# L298.net
KiCad netlist of a schematic drawn in Altium Designer
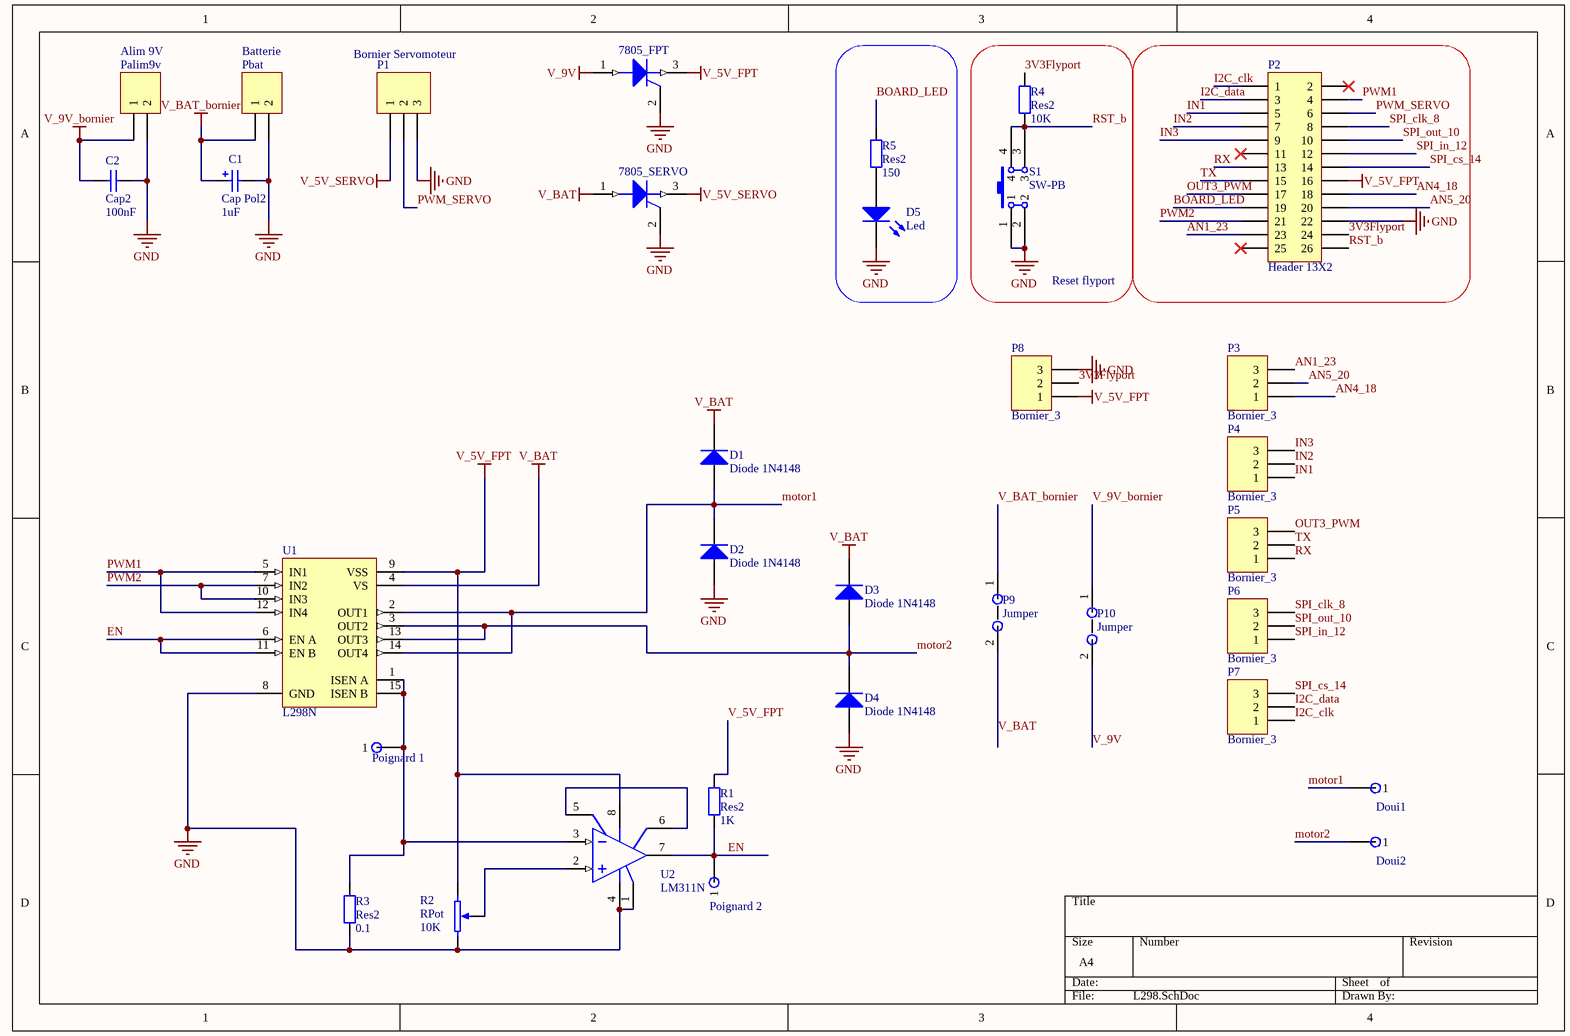
[diagram p0: L298.SchDoc]

(export (version "E")
  (design (tool "Eeschema 10.0.6"))
  (components
    (comp (ref "7805_FPT")
      (value "SCR")
      (footprint "TO-220-AB")
      (description "Silicon Controlled Rectifier")
      (fields (field (name "PUBLISHER") "Altium Limited"))
      (libsource (lib "Miscellaneous Devices") (part "SCR"))
    )
    (comp (ref "7805_SERVO")
      (value "SCR")
      (footprint "TO-220-AB")
      (description "Silicon Controlled Rectifier")
      (fields (field (name "PUBLISHER") "Altium Limited"))
      (libsource (lib "Miscellaneous Devices") (part "SCR"))
    )
    (comp (ref "C1")
      (value "Cap Pol2")
      (footprint "Capa2_pol")
      (description "Polarized Capacitor (Radial)")
      (fields (field (name "ALTIUM_VALUE") "1uF") (field (name "PUBLISHER") "Altium Limited"))
      (libsource (lib "LIBRAIRIE_INTEGREE_PHELMA1") (part "Cap Pol2"))
    )
    (comp (ref "C2")
      (value "Cap2")
      (footprint "CAPA2")
      (description "Capacitor")
      (fields (field (name "ALTIUM_VALUE") "100nF") (field (name "PUBLISHER") "Altium Limited"))
      (libsource (lib "LIBRAIRIE_INTEGREE_PHELMA1") (part "Cap2"))
    )
    (comp (ref "D1")
      (value "Diode 1N4148")
      (footprint "Ddiode")
      (description "High Conductance Fast Diode")
      (fields (field (name "PUBLISHER") "Altium Limited"))
      (libsource (lib "LIBRAIRIE_INTEGREE_PHELMA1") (part "Diode 1N4148"))
    )
    (comp (ref "D2")
      (value "Diode 1N4148")
      (footprint "Ddiode")
      (description "High Conductance Fast Diode")
      (fields (field (name "PUBLISHER") "Altium Limited"))
      (libsource (lib "LIBRAIRIE_INTEGREE_PHELMA1") (part "Diode 1N4148"))
    )
    (comp (ref "D3")
      (value "Diode 1N4148")
      (footprint "Ddiode")
      (description "High Conductance Fast Diode")
      (fields (field (name "PUBLISHER") "Altium Limited"))
      (libsource (lib "LIBRAIRIE_INTEGREE_PHELMA1") (part "Diode 1N4148"))
    )
    (comp (ref "D4")
      (value "Diode 1N4148")
      (footprint "Ddiode")
      (description "High Conductance Fast Diode")
      (fields (field (name "PUBLISHER") "Altium Limited"))
      (libsource (lib "LIBRAIRIE_INTEGREE_PHELMA1") (part "Diode 1N4148"))
    )
    (comp (ref "D5")
      (value "Led")
      (footprint "LED")
      (description "LED")
      (fields (field (name "PUBLISHER") "Altium Limited"))
      (libsource (lib "LIBRAIRIE_INTEGREE_PHELMA1") (part "Led"))
    )
    (comp (ref "Doui1")
      (value "douille_2mm")
      (footprint "Douille-2mm")
      (description "1-Pin")
      (fields (field (name "PUBLISHER") "Altium Limited"))
      (libsource (lib "INTEGRATED_LIBRARY1_CONNECTEURS") (part "douille_2mm"))
    )
    (comp (ref "Doui2")
      (value "douille_2mm")
      (footprint "Douille-2mm")
      (description "1-Pin")
      (fields (field (name "PUBLISHER") "Altium Limited"))
      (libsource (lib "INTEGRATED_LIBRARY1_CONNECTEURS") (part "douille_2mm"))
    )
    (comp (ref "P1")
      (value "Bornier Servomoteur")
      (footprint "Bornier_3")
      (description "Header, 3-Pin")
      (fields (field (name "PUBLISHER") "Altium Limited"))
      (libsource (lib "") (part "Bornier_3_1"))
    )
    (comp (ref "P2")
      (value "Header 13X2")
      (footprint "HDR2X13")
      (description "Header, 13-Pin, Dual row")
      (fields (field (name "PUBLISHER") "Altium Limited"))
      (libsource (lib "Miscellaneous Connectors") (part "Header 13X2"))
    )
    (comp (ref "P3")
      (value "Bornier_3")
      (footprint "Bornier_3")
      (description "Header, 3-Pin")
      (fields (field (name "PUBLISHER") "Altium Limited"))
      (libsource (lib "INTEGRATED_LIBRARY1_CONNECTEURS") (part "Bornier_3"))
    )
    (comp (ref "P4")
      (value "Bornier_3")
      (footprint "Bornier_3")
      (description "Header, 3-Pin")
      (fields (field (name "PUBLISHER") "Altium Limited"))
      (libsource (lib "INTEGRATED_LIBRARY1_CONNECTEURS") (part "Bornier_3"))
    )
    (comp (ref "P5")
      (value "Bornier_3")
      (footprint "Bornier_3")
      (description "Header, 3-Pin")
      (fields (field (name "PUBLISHER") "Altium Limited"))
      (libsource (lib "INTEGRATED_LIBRARY1_CONNECTEURS") (part "Bornier_3"))
    )
    (comp (ref "P6")
      (value "Bornier_3")
      (footprint "Bornier_3")
      (description "Header, 3-Pin")
      (fields (field (name "PUBLISHER") "Altium Limited"))
      (libsource (lib "INTEGRATED_LIBRARY1_CONNECTEURS") (part "Bornier_3"))
    )
    (comp (ref "P7")
      (value "Bornier_3")
      (footprint "Bornier_3")
      (description "Header, 3-Pin")
      (fields (field (name "PUBLISHER") "Altium Limited"))
      (libsource (lib "INTEGRATED_LIBRARY1_CONNECTEURS") (part "Bornier_3"))
    )
    (comp (ref "P8")
      (value "Bornier_3")
      (footprint "Bornier_3")
      (description "Header, 3-Pin")
      (fields (field (name "PUBLISHER") "Altium Limited"))
      (libsource (lib "INTEGRATED_LIBRARY1_CONNECTEURS") (part "Bornier_3"))
    )
    (comp (ref "P9")
      (value "Jumper")
      (footprint "picot2")
      (fields (field (name "PUBLISHER") "Altium Limited"))
      (libsource (lib "INTEGRATED_LIBRARY1_CONNECTEURS") (part "Jumper"))
    )
    (comp (ref "P10")
      (value "Jumper")
      (footprint "picot2")
      (fields (field (name "PUBLISHER") "Altium Limited"))
      (libsource (lib "INTEGRATED_LIBRARY1_CONNECTEURS") (part "Jumper"))
    )
    (comp (ref "Palim9v")
      (value "Alim 9V")
      (footprint "Bornier_2")
      (description "Header, 2-Pin")
      (fields (field (name "PUBLISHER") "Altium Limited"))
      (libsource (lib "INTEGRATED_LIBRARY1_CONNECTEURS") (part "Bornier_2"))
    )
    (comp (ref "Pbat")
      (value "Batterie")
      (footprint "Bornier_2")
      (description "Header, 2-Pin")
      (fields (field (name "PUBLISHER") "Altium Limited"))
      (libsource (lib "INTEGRATED_LIBRARY1_CONNECTEURS") (part "Bornier_2"))
    )
    (comp (ref "Poignard 1")
      (value "Poignard")
      (footprint "Poignard")
      (fields (field (name "PUBLISHER") "Altium Limited"))
      (libsource (lib "INTEGRATED_LIBRARY1_CONNECTEURS") (part "Poignard"))
    )
    (comp (ref "Poignard 2")
      (value "Poignard")
      (footprint "Poignard")
      (fields (field (name "PUBLISHER") "Altium Limited"))
      (libsource (lib "INTEGRATED_LIBRARY1_CONNECTEURS") (part "Poignard"))
    )
    (comp (ref "R1")
      (value "Res2")
      (footprint "res5_1/4W")
      (description "Resistor")
      (fields (field (name "ALTIUM_VALUE") "1K") (field (name "PUBLISHER") "Altium Limited"))
      (libsource (lib "") (part "Res2_1"))
    )
    (comp (ref "R2")
      (value "RPot")
      (footprint "AJUSTABLE")
      (description "Potentiometer")
      (fields (field (name "ALTIUM_VALUE") "10K") (field (name "PUBLISHER") "Altium Limited"))
      (libsource (lib "LIBRAIRIE_INTEGREE_PHELMA1") (part "RPot"))
    )
    (comp (ref "R3")
      (value "Res2")
      (footprint "res5_1/4W")
      (description "Resistor")
      (fields (field (name "ALTIUM_VALUE") "0.1") (field (name "PUBLISHER") "Altium Limited"))
      (libsource (lib "LIBRAIRIE_INTEGREE_PHELMA1") (part "Res2"))
    )
    (comp (ref "R4")
      (value "Res2")
      (footprint "res5_1/4W")
      (description "Resistor")
      (fields (field (name "ALTIUM_VALUE") "10K") (field (name "PUBLISHER") "Altium Limited"))
      (libsource (lib "LIBRAIRIE_INTEGREE_PHELMA1") (part "Res2"))
    )
    (comp (ref "R5")
      (value "Res2")
      (footprint "res5_1/4W")
      (description "Resistor")
      (fields (field (name "ALTIUM_VALUE") "150") (field (name "PUBLISHER") "Altium Limited"))
      (libsource (lib "LIBRAIRIE_INTEGREE_PHELMA1") (part "Res2"))
    )
    (comp (ref "S1")
      (value "SW-PB")
      (footprint "SW_BP")
      (description "Switch")
      (fields (field (name "PUBLISHER") "Altium Limited"))
      (libsource (lib "INTEGRATED_LIBRARY1_CONNECTEURS") (part "SW-PB"))
    )
    (comp (ref "U1")
      (value "L298N")
      (footprint "Multiwatt15V")
      (description "Dual Full Bridge Driver")
      (fields (field (name "PUBLISHER") "Altium Limited"))
      (libsource (lib "ST Interface DC Motor Controller") (part "L298N"))
    )
    (comp (ref "U2")
      (value "LM311N")
      (footprint "DIP8")
      (description "Voltage Comparator")
      (fields (field (name "PUBLISHER") "Altium Limited"))
      (libsource (lib "LIBRAIRIE_INTEGREE_PHELMA1") (part "LM311N"))
    )
  )
  (nets
    (net (code "1") (name "/3V3Flyport") (class "Default")
      (node (ref "P2") (pin "24") (pinfunction "24_24") (pintype "passive"))
      (node (ref "P8") (pin "2") (pinfunction "2_2") (pintype "passive"))
      (node (ref "R4") (pin "1") (pinfunction "1_1") (pintype "passive"))
    )
    (net (code "2") (name "/AN1_23") (class "Default")
      (node (ref "P2") (pin "23") (pinfunction "23_23") (pintype "passive"))
      (node (ref "P3") (pin "3") (pinfunction "3_3") (pintype "passive"))
    )
    (net (code "3") (name "/AN4_18") (class "Default")
      (node (ref "P2") (pin "18") (pinfunction "18_18") (pintype "passive"))
      (node (ref "P3") (pin "1") (pinfunction "1_1") (pintype "passive"))
    )
    (net (code "4") (name "/AN5_20") (class "Default")
      (node (ref "P2") (pin "20") (pinfunction "20_20") (pintype "passive"))
      (node (ref "P3") (pin "2") (pinfunction "2_2") (pintype "passive"))
    )
    (net (code "5") (name "/BOARD_LED") (class "Default")
      (node (ref "P2") (pin "19") (pinfunction "19_19") (pintype "passive"))
      (node (ref "R5") (pin "1") (pinfunction "1_1") (pintype "passive"))
    )
    (net (code "6") (name "/EN") (class "Default")
      (node (ref "Poignard 2") (pin "1") (pinfunction "1_1") (pintype "passive"))
      (node (ref "R1") (pin "1") (pinfunction "1_1") (pintype "passive"))
      (node (ref "U1") (pin "11") (pinfunction "EN_B_11") (pintype "input"))
      (node (ref "U1") (pin "6") (pinfunction "EN_A_6") (pintype "input"))
      (node (ref "U2") (pin "7") (pinfunction "OUT_7") (pintype "open_collector"))
    )
    (net (code "7") (name "/I2C_clk") (class "Default")
      (node (ref "P2") (pin "1") (pinfunction "1_1") (pintype "passive"))
      (node (ref "P7") (pin "1") (pinfunction "1_1") (pintype "passive"))
    )
    (net (code "8") (name "/I2C_data") (class "Default")
      (node (ref "P2") (pin "3") (pinfunction "3_3") (pintype "passive"))
      (node (ref "P7") (pin "2") (pinfunction "2_2") (pintype "passive"))
    )
    (net (code "9") (name "/IN1") (class "Default")
      (node (ref "P2") (pin "5") (pinfunction "5_5") (pintype "passive"))
      (node (ref "P4") (pin "1") (pinfunction "1_1") (pintype "passive"))
    )
    (net (code "10") (name "/IN2") (class "Default")
      (node (ref "P2") (pin "7") (pinfunction "7_7") (pintype "passive"))
      (node (ref "P4") (pin "2") (pinfunction "2_2") (pintype "passive"))
    )
    (net (code "11") (name "/IN3") (class "Default")
      (node (ref "P2") (pin "9") (pinfunction "9_9") (pintype "passive"))
      (node (ref "P4") (pin "3") (pinfunction "3_3") (pintype "passive"))
    )
    (net (code "12") (name "/OUT3_PWM") (class "Default")
      (node (ref "P2") (pin "17") (pinfunction "17_17") (pintype "passive"))
      (node (ref "P5") (pin "3") (pinfunction "3_3") (pintype "passive"))
    )
    (net (code "13") (name "/PWM1") (class "Default")
      (node (ref "P2") (pin "4") (pinfunction "4_4") (pintype "passive"))
      (node (ref "U1") (pin "12") (pinfunction "IN4_12") (pintype "input"))
      (node (ref "U1") (pin "5") (pinfunction "IN1_5") (pintype "input"))
    )
    (net (code "14") (name "/PWM2") (class "Default")
      (node (ref "P2") (pin "21") (pinfunction "21_21") (pintype "passive"))
      (node (ref "U1") (pin "10") (pinfunction "IN3_10") (pintype "input"))
      (node (ref "U1") (pin "7") (pinfunction "IN2_7") (pintype "input"))
    )
    (net (code "15") (name "/PWM_SERVO") (class "Default")
      (node (ref "P1") (pin "2") (pinfunction "2_2") (pintype "passive"))
      (node (ref "P2") (pin "6") (pinfunction "6_6") (pintype "passive"))
    )
    (net (code "16") (name "/RST_b") (class "Default")
      (node (ref "P2") (pin "26") (pinfunction "26_26") (pintype "passive"))
      (node (ref "R4") (pin "2") (pinfunction "2_2") (pintype "passive"))
      (node (ref "S1") (pin "3") (pinfunction "3_3") (pintype "passive"))
      (node (ref "S1") (pin "4") (pinfunction "4_4") (pintype "passive"))
    )
    (net (code "17") (name "/RX") (class "Default")
      (node (ref "P2") (pin "13") (pinfunction "13_13") (pintype "passive"))
      (node (ref "P5") (pin "1") (pinfunction "1_1") (pintype "passive"))
    )
    (net (code "18") (name "/SPI_clk_8") (class "Default")
      (node (ref "P2") (pin "8") (pinfunction "8_8") (pintype "passive"))
      (node (ref "P6") (pin "3") (pinfunction "3_3") (pintype "passive"))
    )
    (net (code "19") (name "/SPI_cs_14") (class "Default")
      (node (ref "P2") (pin "14") (pinfunction "14_14") (pintype "passive"))
      (node (ref "P7") (pin "3") (pinfunction "3_3") (pintype "passive"))
    )
    (net (code "20") (name "/SPI_in_12") (class "Default")
      (node (ref "P2") (pin "12") (pinfunction "12_12") (pintype "passive"))
      (node (ref "P6") (pin "1") (pinfunction "1_1") (pintype "passive"))
    )
    (net (code "21") (name "/SPI_out_10") (class "Default")
      (node (ref "P2") (pin "10") (pinfunction "10_10") (pintype "passive"))
      (node (ref "P6") (pin "2") (pinfunction "2_2") (pintype "passive"))
    )
    (net (code "22") (name "/TX") (class "Default")
      (node (ref "P2") (pin "15") (pinfunction "15_15") (pintype "passive"))
      (node (ref "P5") (pin "2") (pinfunction "2_2") (pintype "passive"))
    )
    (net (code "23") (name "/motor1") (class "Default")
      (node (ref "D1") (pin "1") (pinfunction "A_1") (pintype "passive"))
      (node (ref "D2") (pin "2") (pinfunction "K_2") (pintype "passive"))
      (node (ref "Doui1") (pin "1") (pinfunction "1_1") (pintype "passive"))
      (node (ref "U1") (pin "14") (pinfunction "OUT4_14") (pintype "output"))
      (node (ref "U1") (pin "2") (pinfunction "OUT1_2") (pintype "output"))
    )
    (net (code "24") (name "/motor2") (class "Default")
      (node (ref "D3") (pin "1") (pinfunction "A_1") (pintype "passive"))
      (node (ref "D4") (pin "2") (pinfunction "K_2") (pintype "passive"))
      (node (ref "Doui2") (pin "1") (pinfunction "1_1") (pintype "passive"))
      (node (ref "U1") (pin "13") (pinfunction "OUT3_13") (pintype "output"))
      (node (ref "U1") (pin "3") (pinfunction "OUT2_3") (pintype "output"))
    )
    (net (code "25") (name "GND") (class "Default")
      (node (ref "7805_FPT") (pin "2") (pinfunction "GND_2") (pintype "power_in"))
      (node (ref "7805_SERVO") (pin "2") (pinfunction "GND_2") (pintype "power_in"))
      (node (ref "C1") (pin "2") (pinfunction "2_2") (pintype "passive"))
      (node (ref "C2") (pin "2") (pinfunction "2_2") (pintype "passive"))
      (node (ref "D2") (pin "1") (pinfunction "A_1") (pintype "passive"))
      (node (ref "D4") (pin "1") (pinfunction "A_1") (pintype "passive"))
      (node (ref "D5") (pin "2") (pinfunction "K_2") (pintype "passive"))
      (node (ref "P1") (pin "3") (pinfunction "3_3") (pintype "passive"))
      (node (ref "P2") (pin "22") (pinfunction "22_22") (pintype "passive"))
      (node (ref "P8") (pin "3") (pinfunction "3_3") (pintype "passive"))
      (node (ref "Palim9v") (pin "2") (pinfunction "2_2") (pintype "passive"))
      (node (ref "Pbat") (pin "2") (pinfunction "2_2") (pintype "passive"))
      (node (ref "R2") (pin "3") (pinfunction "TOP_3") (pintype "passive"))
      (node (ref "R3") (pin "2") (pinfunction "2_2") (pintype "passive"))
      (node (ref "S1") (pin "1") (pinfunction "1_1") (pintype "passive"))
      (node (ref "S1") (pin "2") (pinfunction "2_2") (pintype "passive"))
      (node (ref "U1") (pin "8") (pinfunction "GND_8") (pintype "power_in"))
      (node (ref "U2") (pin "1") (pinfunction "GND_1") (pintype "power_in"))
      (node (ref "U2") (pin "4") (pinfunction "V-_(CASE)_4") (pintype "power_in"))
    )
    (net (code "26") (name "Net-(D5-A)") (class "Default")
      (node (ref "D5") (pin "1") (pinfunction "A_1") (pintype "passive"))
      (node (ref "R5") (pin "2") (pinfunction "2_2") (pintype "passive"))
    )
    (net (code "27") (name "Net-(R2-TAP)") (class "Default")
      (node (ref "R2") (pin "2") (pinfunction "TAP_2") (pintype "passive"))
      (node (ref "U2") (pin "2") (pinfunction "IN+_2") (pintype "input"))
    )
    (net (code "28") (name "Net-(U1-ISEN_A)") (class "Default")
      (node (ref "Poignard 1") (pin "1") (pinfunction "1_1") (pintype "passive"))
      (node (ref "R3") (pin "1") (pinfunction "1_1") (pintype "passive"))
      (node (ref "U1") (pin "1") (pinfunction "ISEN_A_1") (pintype "passive"))
      (node (ref "U1") (pin "15") (pinfunction "ISEN_B_15") (pintype "passive"))
      (node (ref "U2") (pin "3") (pinfunction "IN-_3") (pintype "input"))
    )
    (net (code "29") (name "Net-(U2-BAL)") (class "Default")
      (node (ref "U2") (pin "5") (pinfunction "BAL_5") (pintype "passive"))
      (node (ref "U2") (pin "6") (pinfunction "BAL/STB_6") (pintype "passive"))
    )
    (net (code "30") (name "V_5V_FPT") (class "Default")
      (node (ref "7805_FPT") (pin "3") (pinfunction "OUT_3") (pintype "output"))
      (node (ref "P2") (pin "16") (pinfunction "16_16") (pintype "passive"))
      (node (ref "P8") (pin "1") (pinfunction "1_1") (pintype "passive"))
      (node (ref "R1") (pin "2") (pinfunction "2_2") (pintype "passive"))
      (node (ref "R2") (pin "1") (pinfunction "BOT_1") (pintype "passive"))
      (node (ref "U1") (pin "9") (pinfunction "VSS_9") (pintype "power_in"))
      (node (ref "U2") (pin "8") (pinfunction "V+_8") (pintype "power_in"))
    )
    (net (code "31") (name "V_5V_SERVO") (class "Default")
      (node (ref "7805_SERVO") (pin "3") (pinfunction "OUT_3") (pintype "output"))
      (node (ref "P1") (pin "1") (pinfunction "1_1") (pintype "passive"))
    )
    (net (code "32") (name "V_9V") (class "Default")
      (node (ref "7805_FPT") (pin "1") (pinfunction "IN_1") (pintype "input"))
      (node (ref "P10") (pin "2") (pinfunction "2_2") (pintype "passive"))
    )
    (net (code "33") (name "V_9V_bornier") (class "Default")
      (node (ref "C2") (pin "1") (pinfunction "1_1") (pintype "passive"))
      (node (ref "P10") (pin "1") (pinfunction "1_1") (pintype "passive"))
      (node (ref "Palim9v") (pin "1") (pinfunction "1_1") (pintype "passive"))
    )
    (net (code "34") (name "V_BAT") (class "Default")
      (node (ref "7805_SERVO") (pin "1") (pinfunction "IN_1") (pintype "input"))
      (node (ref "D1") (pin "2") (pinfunction "K_2") (pintype "passive"))
      (node (ref "D3") (pin "2") (pinfunction "K_2") (pintype "passive"))
      (node (ref "P9") (pin "2") (pinfunction "2_2") (pintype "passive"))
      (node (ref "U1") (pin "4") (pinfunction "VS_4") (pintype "power_in"))
    )
    (net (code "35") (name "V_BAT_bornier") (class "Default")
      (node (ref "C1") (pin "1") (pinfunction "1_1") (pintype "passive"))
      (node (ref "P9") (pin "1") (pinfunction "1_1") (pintype "passive"))
      (node (ref "Pbat") (pin "1") (pinfunction "1_1") (pintype "passive"))
    )
    (net (code "36") (name "unconnected-(P2-Pad2)") (class "Default")
      (node (ref "P2") (pin "2") (pinfunction "2_2") (pintype "passive+no_connect"))
    )
    (net (code "37") (name "unconnected-(P2-Pad11)") (class "Default")
      (node (ref "P2") (pin "11") (pinfunction "11_11") (pintype "passive+no_connect"))
    )
    (net (code "38") (name "unconnected-(P2-Pad25)") (class "Default")
      (node (ref "P2") (pin "25") (pinfunction "25_25") (pintype "passive+no_connect"))
    )
  )
)
